# teensyPlayback.net
KiCad netlist of a schematic drawn in Altium Designer
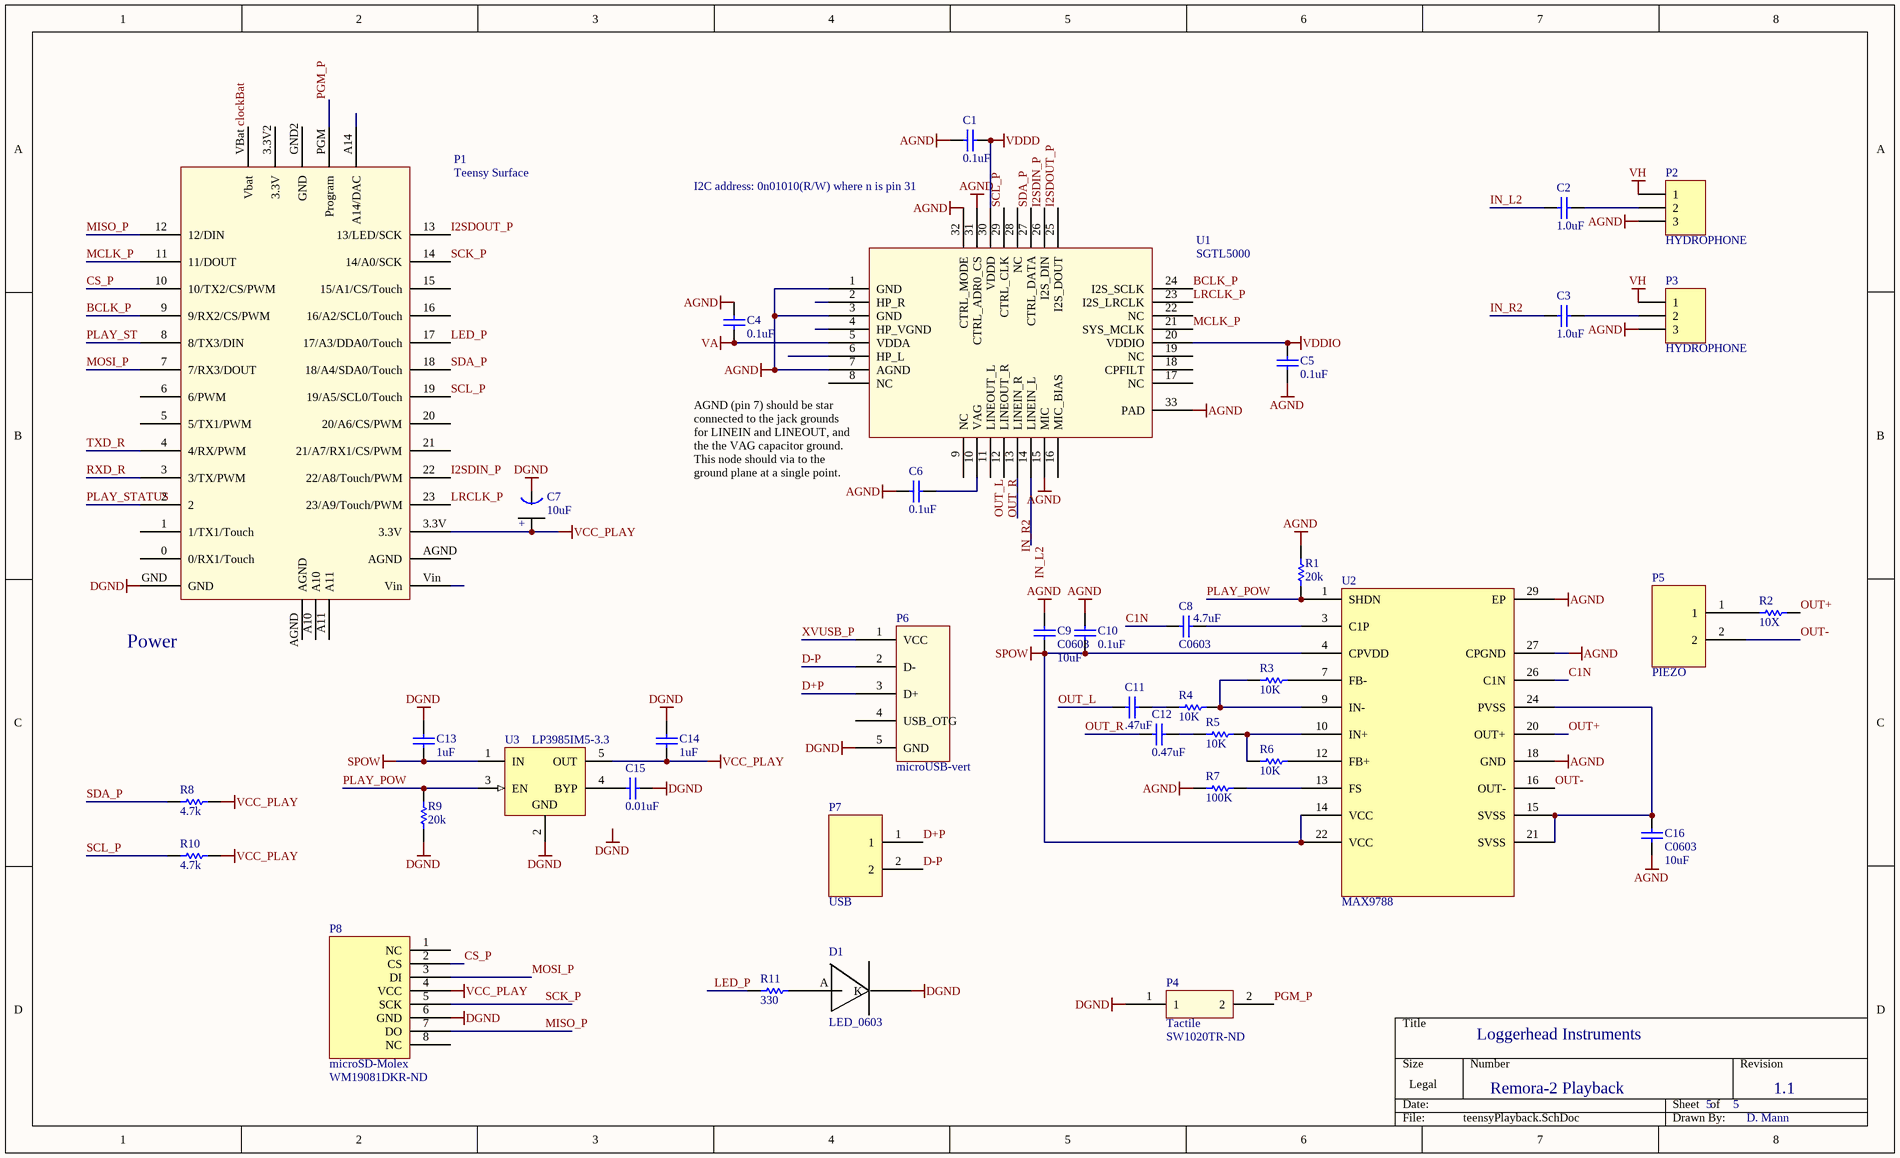
[diagram p0: teensyPlayback.SchDoc]

(export (version "E")
  (design (tool "Eeschema 10.0.6"))
  (components
    (comp (ref "C1")
      (value "0.1uF")
      (footprint "0402")
      (description "Ceramic Chip Capacitor - Standard")
      (fields (field (name "PUBLISHER") "Altium Limited"))
      (libsource (lib "KEMET Chip Capacitor") (part "C0402"))
    )
    (comp (ref "C2")
      (value "1.0uF")
      (footprint "0402")
      (description "Ceramic Chip Capacitor - Standard")
      (fields (field (name "PUBLISHER") "Altium Limited"))
      (libsource (lib "KEMET Chip Capacitor") (part "C0402"))
    )
    (comp (ref "C3")
      (value "1.0uF")
      (footprint "0402")
      (description "Ceramic Chip Capacitor - Standard")
      (fields (field (name "PUBLISHER") "Altium Limited"))
      (libsource (lib "KEMET Chip Capacitor") (part "C0402"))
    )
    (comp (ref "C4")
      (value "0.1uF")
      (footprint "0402")
      (description "Ceramic Chip Capacitor - Standard")
      (fields (field (name "PUBLISHER") "Altium Limited"))
      (libsource (lib "KEMET Chip Capacitor") (part "C0402"))
    )
    (comp (ref "C5")
      (value "0.1uF")
      (footprint "0402")
      (description "Ceramic Chip Capacitor - Standard")
      (fields (field (name "PUBLISHER") "Altium Limited"))
      (libsource (lib "KEMET Chip Capacitor") (part "C0402"))
    )
    (comp (ref "C6")
      (value "0.1uF")
      (footprint "0402")
      (description "Ceramic Chip Capacitor - Standard")
      (fields (field (name "PUBLISHER") "Altium Limited"))
      (libsource (lib "KEMET Chip Capacitor") (part "C0402"))
    )
    (comp (ref "C7") (value "10uF") (footprint "Tant0805") (libsource (lib "Loggerhead") (part "Tant0805")))
    (comp (ref "C8")
      (value "C0603")
      (footprint "0603")
      (description "Ceramic Chip Capacitor - Standard")
      (fields (field (name "ALTIUM_VALUE") "4.7uF") (field (name "PUBLISHER") "Altium Limited"))
      (libsource (lib "KEMET Chip Capacitor") (part "C0603"))
    )
    (comp (ref "C9")
      (value "C0603")
      (footprint "0603")
      (description "Ceramic Chip Capacitor - Standard")
      (fields (field (name "ALTIUM_VALUE") "10uF") (field (name "PUBLISHER") "Altium Limited"))
      (libsource (lib "KEMET Chip Capacitor") (part "C0603"))
    )
    (comp (ref "C10")
      (value "0.1uF")
      (footprint "0402")
      (description "Ceramic Chip Capacitor - Standard")
      (fields (field (name "PUBLISHER") "Altium Limited"))
      (libsource (lib "KEMET Chip Capacitor") (part "C0402"))
    )
    (comp (ref "C11")
      (value ".47uF")
      (footprint "0402")
      (description "Ceramic Chip Capacitor - Standard")
      (fields (field (name "PUBLISHER") "Altium Limited"))
      (libsource (lib "KEMET Chip Capacitor") (part "C0402"))
    )
    (comp (ref "C12")
      (value "0.47uF")
      (footprint "0402")
      (description "Ceramic Chip Capacitor - Standard")
      (fields (field (name "PUBLISHER") "Altium Limited"))
      (libsource (lib "KEMET Chip Capacitor") (part "C0402"))
    )
    (comp (ref "C13")
      (value "1uF")
      (footprint "0402")
      (description "Ceramic Chip Capacitor - Standard")
      (fields (field (name "PUBLISHER") "Altium Limited"))
      (libsource (lib "KEMET Chip Capacitor") (part "C0402"))
    )
    (comp (ref "C14")
      (value "1uF")
      (footprint "0402")
      (description "Ceramic Chip Capacitor - Standard")
      (fields (field (name "PUBLISHER") "Altium Limited"))
      (libsource (lib "KEMET Chip Capacitor") (part "C0402"))
    )
    (comp (ref "C15")
      (value "0.01uF")
      (footprint "0402")
      (description "Ceramic Chip Capacitor - Standard")
      (fields (field (name "PUBLISHER") "Altium Limited"))
      (libsource (lib "KEMET Chip Capacitor") (part "C0402"))
    )
    (comp (ref "C16")
      (value "C0603")
      (footprint "0603")
      (description "Ceramic Chip Capacitor - Standard")
      (fields (field (name "ALTIUM_VALUE") "10uF") (field (name "PUBLISHER") "Altium Limited"))
      (libsource (lib "KEMET Chip Capacitor") (part "C0603"))
    )
    (comp (ref "D1")
      (value "LED_0603")
      (footprint "Diode0603")
      (libsource (lib "Loggerhead") (part "LED_0603"))
    )
    (comp (ref "P1")
      (value "Teensy Surface")
      (footprint "TEENSY3.2_surface_mount")
      (libsource (lib "Teensy") (part "Teensy3.2_surface_mount"))
    )
    (comp (ref "P2")
      (value "HYDROPHONE")
      (footprint "HDR1X3")
      (description "Header, 3-Pin")
      (fields (field (name "PUBLISHER") "Altium Limited"))
      (libsource (lib "Miscellaneous Connectors") (part "Header 3"))
    )
    (comp (ref "P3")
      (value "HYDROPHONE")
      (footprint "HDR1X3")
      (description "Header, 3-Pin")
      (fields (field (name "PUBLISHER") "Altium Limited"))
      (libsource (lib "Miscellaneous Connectors") (part "Header 3"))
    )
    (comp (ref "P4")
      (value "Tactile")
      (footprint "Tactile-B3U-1000")
      (fields (field (name "SUPPLIER PART NUMBER 1") "SW1020TR-ND"))
      (libsource (lib "Loggerhead") (part "Tactile_B3U-1000"))
    )
    (comp (ref "P5")
      (value "PIEZO")
      (footprint "HDR_2x1_2mm")
      (description "Charging Connector")
      (libsource (lib "Loggerhead") (part "HDR_2x1_2mm"))
    )
    (comp (ref "P6")
      (value "microUSB-vert")
      (footprint "MICROUSB-VERT")
      (description "Molex 105133-0011")
      (libsource (lib "Loggerhead") (part "microUSB-vert"))
    )
    (comp (ref "P7")
      (value "USB")
      (footprint "HDR_2x1_2mm")
      (description "Charging Connector")
      (libsource (lib "Loggerhead") (part "HDR_2x1_2mm"))
    )
    (comp (ref "P8")
      (value "microSD-Molex")
      (footprint "microSD_Molex_hinged")
      (fields (field (name "SUPPLIER PART NUMBER 1") "WM19081DKR-ND"))
      (libsource (lib "Loggerhead") (part "microSD_Molex_hinged"))
    )
    (comp (ref "R1")
      (value "20k")
      (footprint "3-0603")
      (fields (field (name "PUBLISHER") "Altium Limited"))
      (libsource (lib "Panasonic Resistor") (part "ERJ3RK"))
    )
    (comp (ref "R2")
      (value "10X")
      (footprint "3-0603")
      (fields (field (name "PUBLISHER") "Altium Limited"))
      (libsource (lib "Panasonic Resistor") (part "ERJ3RK"))
    )
    (comp (ref "R3")
      (value "10K")
      (footprint "3-0603")
      (fields (field (name "PUBLISHER") "Altium Limited"))
      (libsource (lib "Panasonic Resistor") (part "ERJ3RK"))
    )
    (comp (ref "R4")
      (value "10K")
      (footprint "3-0603")
      (fields (field (name "PUBLISHER") "Altium Limited"))
      (libsource (lib "Panasonic Resistor") (part "ERJ3RK"))
    )
    (comp (ref "R5")
      (value "10K")
      (footprint "3-0603")
      (fields (field (name "PUBLISHER") "Altium Limited"))
      (libsource (lib "Panasonic Resistor") (part "ERJ3RK"))
    )
    (comp (ref "R6")
      (value "10K")
      (footprint "3-0603")
      (fields (field (name "PUBLISHER") "Altium Limited"))
      (libsource (lib "Panasonic Resistor") (part "ERJ3RK"))
    )
    (comp (ref "R7")
      (value "100K")
      (footprint "3-0603")
      (fields (field (name "PUBLISHER") "Altium Limited"))
      (libsource (lib "Panasonic Resistor") (part "ERJ3RK"))
    )
    (comp (ref "R8")
      (value "4.7k")
      (footprint "3-0603")
      (fields (field (name "PUBLISHER") "Altium Limited"))
      (libsource (lib "Panasonic Resistor") (part "ERJ3RK"))
    )
    (comp (ref "R9")
      (value "20k")
      (footprint "3-0603")
      (fields (field (name "PUBLISHER") "Altium Limited"))
      (libsource (lib "Panasonic Resistor") (part "ERJ3RK"))
    )
    (comp (ref "R10")
      (value "4.7k")
      (footprint "3-0603")
      (fields (field (name "PUBLISHER") "Altium Limited"))
      (libsource (lib "Panasonic Resistor") (part "ERJ3RK"))
    )
    (comp (ref "R11")
      (value "330")
      (footprint "3-0603")
      (fields (field (name "PUBLISHER") "Altium Limited"))
      (libsource (lib "Panasonic Resistor") (part "ERJ3RK"))
    )
    (comp (ref "U1") (value "SGTL5000") (footprint "QFN32") (libsource (lib "Loggerhead") (part "SGTL5000")))
    (comp (ref "U2")
      (value "MAX9788")
      (footprint "MAX9788")
      (description "audio amp")
      (libsource (lib "Loggerhead") (part "MAX9788"))
    )
    (comp (ref "U3")
      (value "LP3985IM5-3.3")
      (footprint "MF05A_N")
      (description "Micropower, 150mA Low-Noise Ultra Low-Dropout CMOS Voltage Regulator")
      (fields
        (field (name "MANUFACTURER") "National Semiconductor")
        (field (name "DIGIKEYPARTNUMBER") "LP3985IM5-3.3CT-ND")
        (field (name "PUBLISHER") "Altium Limited")
      )
      (libsource (lib "NSC LDO") (part "LP3985IM5-3.3"))
    )
  )
  (nets
    (net (code "1") (name "/BCLK_P") (class "Default")
      (node (ref "P1") (pin "9") (pinfunction "9/RX2/CS/PWM_9") (pintype "passive"))
      (node (ref "U1") (pin "24") (pinfunction "I2S_SCLK_24") (pintype "passive"))
    )
    (net (code "2") (name "/C1N") (class "Default")
      (node (ref "C8") (pin "1") (pinfunction "1_1") (pintype "passive"))
      (node (ref "U2") (pin "26") (pinfunction "C1N_26") (pintype "passive"))
    )
    (net (code "3") (name "/CS_P") (class "Default")
      (node (ref "P1") (pin "10") (pinfunction "10/TX2/CS/PWM_10") (pintype "passive"))
      (node (ref "P8") (pin "2") (pinfunction "CS_2") (pintype "passive"))
    )
    (net (code "4") (name "/D+P") (class "Default")
      (node (ref "P6") (pin "3") (pinfunction "D+_3") (pintype "passive"))
      (node (ref "P7") (pin "1") (pinfunction "1_1") (pintype "passive"))
    )
    (net (code "5") (name "/D-P") (class "Default")
      (node (ref "P6") (pin "2") (pinfunction "D-_2") (pintype "passive"))
      (node (ref "P7") (pin "2") (pinfunction "2_2") (pintype "passive"))
    )
    (net (code "6") (name "/I2SDIN_P") (class "Default")
      (node (ref "P1") (pin "22") (pinfunction "22/A8/Touch/PWM_22") (pintype "passive"))
      (node (ref "U1") (pin "26") (pinfunction "I2S_DIN_26") (pintype "passive"))
    )
    (net (code "7") (name "/I2SDOUT_P") (class "Default")
      (node (ref "P1") (pin "13") (pinfunction "13/LED/SCK_13") (pintype "passive"))
      (node (ref "U1") (pin "25") (pinfunction "I2S_DOUT_25") (pintype "passive"))
    )
    (net (code "8") (name "/IN_L2") (class "Default")
      (node (ref "C2") (pin "2") (pinfunction "2_2") (pintype "passive"))
      (node (ref "U1") (pin "14") (pinfunction "LINEIN_L_14") (pintype "passive"))
    )
    (net (code "9") (name "/IN_R2") (class "Default")
      (node (ref "C3") (pin "2") (pinfunction "2_2") (pintype "passive"))
      (node (ref "U1") (pin "13") (pinfunction "LINEIN_R_13") (pintype "passive"))
    )
    (net (code "10") (name "/LED_P") (class "Default")
      (node (ref "P1") (pin "17") (pinfunction "17/A3/DDA0/Touch_17") (pintype "passive"))
      (node (ref "R11") (pin "1") (pinfunction "1_1") (pintype "passive"))
    )
    (net (code "11") (name "/LRCLK_P") (class "Default")
      (node (ref "P1") (pin "23") (pinfunction "23/A9/Touch/PWM_23") (pintype "passive"))
      (node (ref "U1") (pin "23") (pinfunction "I2S_LRCLK_23") (pintype "passive"))
    )
    (net (code "12") (name "/MCLK_P") (class "Default")
      (node (ref "P1") (pin "11") (pinfunction "11/DOUT_11") (pintype "passive"))
      (node (ref "U1") (pin "21") (pinfunction "SYS_MCLK_21") (pintype "passive"))
    )
    (net (code "13") (name "/MISO_P") (class "Default")
      (node (ref "P1") (pin "12") (pinfunction "12/DIN_12") (pintype "passive"))
      (node (ref "P8") (pin "7") (pinfunction "DO_7") (pintype "passive"))
    )
    (net (code "14") (name "/MOSI_P") (class "Default")
      (node (ref "P1") (pin "7") (pinfunction "7/RX3/DOUT_7") (pintype "passive"))
      (node (ref "P8") (pin "3") (pinfunction "DI_3") (pintype "passive"))
    )
    (net (code "15") (name "/OUT+") (class "Default")
      (node (ref "R2") (pin "1") (pinfunction "1_1") (pintype "passive"))
      (node (ref "U2") (pin "20") (pinfunction "OUT+_20") (pintype "passive"))
    )
    (net (code "16") (name "/OUT-") (class "Default")
      (node (ref "P5") (pin "2") (pinfunction "2_2") (pintype "passive"))
      (node (ref "U2") (pin "16") (pinfunction "OUT-_16") (pintype "passive"))
    )
    (net (code "17") (name "/OUT_L") (class "Default")
      (node (ref "C11") (pin "2") (pinfunction "2_2") (pintype "passive"))
      (node (ref "U1") (pin "11") (pinfunction "LINEOUT_L_11") (pintype "passive"))
    )
    (net (code "18") (name "/OUT_R") (class "Default")
      (node (ref "C12") (pin "2") (pinfunction "2_2") (pintype "passive"))
      (node (ref "U1") (pin "12") (pinfunction "LINEOUT_R_12") (pintype "passive"))
    )
    (net (code "19") (name "/PGM_P") (class "Default")
      (node (ref "P1") (pin "PGM") (pinfunction "Program_PGM") (pintype "passive"))
      (node (ref "P4") (pin "2") (pinfunction "2_2") (pintype "passive"))
    )
    (net (code "20") (name "/PLAY_POW") (class "Default")
      (node (ref "R1") (pin "2") (pinfunction "2_2") (pintype "passive"))
      (node (ref "R9") (pin "2") (pinfunction "2_2") (pintype "passive"))
      (node (ref "U2") (pin "1") (pinfunction "SHDN_1") (pintype "passive"))
      (node (ref "U3") (pin "3") (pinfunction "EN_3") (pintype "input"))
    )
    (net (code "21") (name "/PLAY_ST") (class "Default")
      (node (ref "P1") (pin "8") (pinfunction "8/TX3/DIN_8") (pintype "passive"))
    )
    (net (code "22") (name "/PLAY_STATUS") (class "Default")
      (node (ref "P1") (pin "2") (pinfunction "2_2") (pintype "passive"))
    )
    (net (code "23") (name "/RXD_R") (class "Default")
      (node (ref "P1") (pin "3") (pinfunction "3/TX/PWM_3") (pintype "passive"))
    )
    (net (code "24") (name "/SCK_P") (class "Default")
      (node (ref "P1") (pin "14") (pinfunction "14/A0/SCK_14") (pintype "passive"))
      (node (ref "P8") (pin "5") (pinfunction "SCK_5") (pintype "passive"))
    )
    (net (code "25") (name "/SCL_P") (class "Default")
      (node (ref "P1") (pin "19") (pinfunction "19/A5/SCL0/Touch_19") (pintype "passive"))
      (node (ref "R10") (pin "1") (pinfunction "1_1") (pintype "passive"))
      (node (ref "U1") (pin "29") (pinfunction "CTRL_CLK_29") (pintype "passive"))
    )
    (net (code "26") (name "/SDA_P") (class "Default")
      (node (ref "P1") (pin "18") (pinfunction "18/A4/SDA0/Touch_18") (pintype "passive"))
      (node (ref "R8") (pin "1") (pinfunction "1_1") (pintype "passive"))
      (node (ref "U1") (pin "27") (pinfunction "CTRL_DATA_27") (pintype "passive"))
    )
    (net (code "27") (name "/TXD_R") (class "Default")
      (node (ref "P1") (pin "4") (pinfunction "4/RX/PWM_4") (pintype "passive"))
    )
    (net (code "28") (name "/XVUSB_P") (class "Default")
      (node (ref "P6") (pin "1") (pinfunction "VCC_1") (pintype "passive"))
    )
    (net (code "29") (name "/clockBat") (class "Default")
      (node (ref "P1") (pin "VBat") (pinfunction "Vbat_VBat") (pintype "passive"))
    )
    (net (code "30") (name "AGND") (class "Default")
      (node (ref "C1") (pin "2") (pinfunction "2_2") (pintype "passive"))
      (node (ref "C10") (pin "2") (pinfunction "2_2") (pintype "passive"))
      (node (ref "C16") (pin "1") (pinfunction "1_1") (pintype "passive"))
      (node (ref "C4") (pin "2") (pinfunction "2_2") (pintype "passive"))
      (node (ref "C5") (pin "2") (pinfunction "2_2") (pintype "passive"))
      (node (ref "C6") (pin "2") (pinfunction "2_2") (pintype "passive"))
      (node (ref "C9") (pin "1") (pinfunction "1_1") (pintype "passive"))
      (node (ref "P2") (pin "3") (pinfunction "3_3") (pintype "passive"))
      (node (ref "P3") (pin "3") (pinfunction "3_3") (pintype "passive"))
      (node (ref "R1") (pin "1") (pinfunction "1_1") (pintype "passive"))
      (node (ref "R7") (pin "1") (pinfunction "1_1") (pintype "passive"))
      (node (ref "U1") (pin "1") (pinfunction "GND_1") (pintype "passive"))
      (node (ref "U1") (pin "15") (pinfunction "MIC_15") (pintype "passive"))
      (node (ref "U1") (pin "3") (pinfunction "GND_3") (pintype "passive"))
      (node (ref "U1") (pin "31") (pinfunction "CTRL_ADR0_CS_31") (pintype "passive"))
      (node (ref "U1") (pin "32") (pinfunction "CTRL_MODE_32") (pintype "passive"))
      (node (ref "U1") (pin "33") (pinfunction "PAD_33") (pintype "passive"))
      (node (ref "U1") (pin "7") (pinfunction "AGND_7") (pintype "passive"))
      (node (ref "U2") (pin "18") (pinfunction "GND_18") (pintype "passive"))
      (node (ref "U2") (pin "27") (pinfunction "CPGND_27") (pintype "passive"))
      (node (ref "U2") (pin "29") (pinfunction "EP_29") (pintype "passive"))
    )
    (net (code "31") (name "DGND") (class "Default")
      (node (ref "C13") (pin "2") (pinfunction "2_2") (pintype "passive"))
      (node (ref "C14") (pin "2") (pinfunction "2_2") (pintype "passive"))
      (node (ref "C15") (pin "2") (pinfunction "2_2") (pintype "passive"))
      (node (ref "C7") (pin "1") (pinfunction "GND_1") (pintype "passive"))
      (node (ref "D1") (pin "K") (pinfunction "K_K") (pintype "passive"))
      (node (ref "P1") (pin "GND") (pinfunction "GND_GND") (pintype "passive"))
      (node (ref "P4") (pin "1") (pinfunction "1_1") (pintype "passive"))
      (node (ref "P6") (pin "5") (pinfunction "GND_5") (pintype "passive"))
      (node (ref "P8") (pin "6") (pinfunction "GND_6") (pintype "passive"))
      (node (ref "R9") (pin "1") (pinfunction "1_1") (pintype "passive"))
      (node (ref "U3") (pin "2") (pinfunction "GND_2") (pintype "power_in"))
    )
    (net (code "32") (name "Net-(C2-Pad1)") (class "Default")
      (node (ref "C2") (pin "1") (pinfunction "1_1") (pintype "passive"))
      (node (ref "P2") (pin "2") (pinfunction "2_2") (pintype "passive"))
    )
    (net (code "33") (name "Net-(C3-Pad1)") (class "Default")
      (node (ref "C3") (pin "1") (pinfunction "1_1") (pintype "passive"))
      (node (ref "P3") (pin "2") (pinfunction "2_2") (pintype "passive"))
    )
    (net (code "34") (name "Net-(C11-Pad1)") (class "Default")
      (node (ref "C11") (pin "1") (pinfunction "1_1") (pintype "passive"))
      (node (ref "R4") (pin "1") (pinfunction "1_1") (pintype "passive"))
    )
    (net (code "35") (name "Net-(C12-Pad1)") (class "Default")
      (node (ref "C12") (pin "1") (pinfunction "1_1") (pintype "passive"))
      (node (ref "R5") (pin "1") (pinfunction "1_1") (pintype "passive"))
    )
    (net (code "36") (name "Net-(D1-PadA)") (class "Default")
      (node (ref "D1") (pin "A") (pinfunction "A_A") (pintype "passive"))
      (node (ref "R11") (pin "2") (pinfunction "2_2") (pintype "passive"))
    )
    (net (code "37") (name "Net-(P5-Pad1)") (class "Default")
      (node (ref "P5") (pin "1") (pinfunction "1_1") (pintype "passive"))
      (node (ref "R2") (pin "2") (pinfunction "2_2") (pintype "passive"))
    )
    (net (code "38") (name "Net-(U1-VAG)") (class "Default")
      (node (ref "C6") (pin "1") (pinfunction "1_1") (pintype "passive"))
      (node (ref "U1") (pin "10") (pinfunction "VAG_10") (pintype "passive"))
    )
    (net (code "39") (name "Net-(U2-C1P)") (class "Default")
      (node (ref "C8") (pin "2") (pinfunction "2_2") (pintype "passive"))
      (node (ref "U2") (pin "3") (pinfunction "C1P_3") (pintype "passive"))
    )
    (net (code "40") (name "Net-(U2-FB+)") (class "Default")
      (node (ref "R6") (pin "2") (pinfunction "2_2") (pintype "passive"))
      (node (ref "U2") (pin "12") (pinfunction "FB+_12") (pintype "passive"))
    )
    (net (code "41") (name "Net-(U2-FB-)") (class "Default")
      (node (ref "R3") (pin "2") (pinfunction "2_2") (pintype "passive"))
      (node (ref "U2") (pin "7") (pinfunction "FB-_7") (pintype "passive"))
    )
    (net (code "42") (name "Net-(U2-FS)") (class "Default")
      (node (ref "R7") (pin "2") (pinfunction "2_2") (pintype "passive"))
      (node (ref "U2") (pin "13") (pinfunction "FS_13") (pintype "passive"))
    )
    (net (code "43") (name "Net-(U2-IN+)") (class "Default")
      (node (ref "R5") (pin "2") (pinfunction "2_2") (pintype "passive"))
      (node (ref "R6") (pin "1") (pinfunction "1_1") (pintype "passive"))
      (node (ref "U2") (pin "10") (pinfunction "IN+_10") (pintype "passive"))
    )
    (net (code "44") (name "Net-(U2-IN-)") (class "Default")
      (node (ref "R3") (pin "1") (pinfunction "1_1") (pintype "passive"))
      (node (ref "R4") (pin "2") (pinfunction "2_2") (pintype "passive"))
      (node (ref "U2") (pin "9") (pinfunction "IN-_9") (pintype "passive"))
    )
    (net (code "45") (name "Net-(U2-PVSS)") (class "Default")
      (node (ref "C16") (pin "2") (pinfunction "2_2") (pintype "passive"))
      (node (ref "U2") (pin "15") (pinfunction "SVSS_15") (pintype "passive"))
      (node (ref "U2") (pin "21") (pinfunction "SVSS_21") (pintype "passive"))
      (node (ref "U2") (pin "24") (pinfunction "PVSS_24") (pintype "passive"))
    )
    (net (code "46") (name "Net-(U3-BYP)") (class "Default")
      (node (ref "C15") (pin "1") (pinfunction "1_1") (pintype "passive"))
      (node (ref "U3") (pin "4") (pinfunction "BYP_4") (pintype "passive"))
    )
    (net (code "47") (name "SPOW") (class "Default")
      (node (ref "C10") (pin "1") (pinfunction "1_1") (pintype "passive"))
      (node (ref "C13") (pin "1") (pinfunction "1_1") (pintype "passive"))
      (node (ref "C9") (pin "2") (pinfunction "2_2") (pintype "passive"))
      (node (ref "U2") (pin "14") (pinfunction "VCC_14") (pintype "passive"))
      (node (ref "U2") (pin "22") (pinfunction "VCC_22") (pintype "passive"))
      (node (ref "U2") (pin "4") (pinfunction "CPVDD_4") (pintype "passive"))
      (node (ref "U3") (pin "1") (pinfunction "IN_1") (pintype "power_in"))
    )
    (net (code "48") (name "VA") (class "Default")
      (node (ref "C4") (pin "1") (pinfunction "1_1") (pintype "passive"))
      (node (ref "U1") (pin "5") (pinfunction "VDDA_5") (pintype "passive"))
    )
    (net (code "49") (name "VCC_PLAY") (class "Default")
      (node (ref "C14") (pin "1") (pinfunction "1_1") (pintype "passive"))
      (node (ref "C7") (pin "2") (pinfunction "+_2") (pintype "passive"))
      (node (ref "P1") (pin "3.3V") (pinfunction "3.3V_3.3V") (pintype "passive"))
      (node (ref "P8") (pin "4") (pinfunction "VCC_4") (pintype "passive"))
      (node (ref "R10") (pin "2") (pinfunction "2_2") (pintype "passive"))
      (node (ref "R8") (pin "2") (pinfunction "2_2") (pintype "passive"))
      (node (ref "U3") (pin "5") (pinfunction "OUT_5") (pintype "power_in"))
    )
    (net (code "50") (name "VDDD") (class "Default")
      (node (ref "C1") (pin "1") (pinfunction "1_1") (pintype "passive"))
      (node (ref "U1") (pin "30") (pinfunction "VDDD_30") (pintype "passive"))
    )
    (net (code "51") (name "VDDIO") (class "Default")
      (node (ref "C5") (pin "1") (pinfunction "1_1") (pintype "passive"))
      (node (ref "U1") (pin "20") (pinfunction "VDDIO_20") (pintype "passive"))
    )
    (net (code "52") (name "VH") (class "Default")
      (node (ref "P2") (pin "1") (pinfunction "1_1") (pintype "passive"))
      (node (ref "P3") (pin "1") (pinfunction "1_1") (pintype "passive"))
    )
    (net (code "53") (name "unconnected-(P1-0{slash}RX1{slash}Touch-Pad0)") (class "Default")
      (node (ref "P1") (pin "0") (pinfunction "0/RX1/Touch_0") (pintype "passive"))
    )
    (net (code "54") (name "unconnected-(P1-1{slash}TX1{slash}Touch-Pad1)") (class "Default")
      (node (ref "P1") (pin "1") (pinfunction "1/TX1/Touch_1") (pintype "passive"))
    )
    (net (code "55") (name "unconnected-(P1-3.3V-Pad3.3V2)") (class "Default")
      (node (ref "P1") (pin "3.3V2") (pinfunction "3.3V_3.3V2") (pintype "passive"))
    )
    (net (code "56") (name "unconnected-(P1-5{slash}TX1{slash}PWM-Pad5)") (class "Default")
      (node (ref "P1") (pin "5") (pinfunction "5/TX1/PWM_5") (pintype "passive"))
    )
    (net (code "57") (name "unconnected-(P1-6{slash}PWM-Pad6)") (class "Default")
      (node (ref "P1") (pin "6") (pinfunction "6/PWM_6") (pintype "passive"))
    )
    (net (code "58") (name "unconnected-(P1-15{slash}A1{slash}CS{slash}Touch-Pad15)") (class "Default")
      (node (ref "P1") (pin "15") (pinfunction "15/A1/CS/Touch_15") (pintype "passive"))
    )
    (net (code "59") (name "unconnected-(P1-16{slash}A2{slash}SCL0{slash}Touch-Pad16)") (class "Default")
      (node (ref "P1") (pin "16") (pinfunction "16/A2/SCL0/Touch_16") (pintype "passive"))
    )
    (net (code "60") (name "unconnected-(P1-20{slash}A6{slash}CS{slash}PWM-Pad20)") (class "Default")
      (node (ref "P1") (pin "20") (pinfunction "20/A6/CS/PWM_20") (pintype "passive"))
    )
    (net (code "61") (name "unconnected-(P1-21{slash}A7{slash}RX1{slash}CS{slash}PWM-Pad21)") (class "Default")
      (node (ref "P1") (pin "21") (pinfunction "21/A7/RX1/CS/PWM_21") (pintype "passive"))
    )
    (net (code "62") (name "unconnected-(P1-A14{slash}DAC-PadA14)") (class "Default")
      (node (ref "P1") (pin "A14") (pinfunction "A14/DAC_A14") (pintype "passive"))
    )
    (net (code "63") (name "unconnected-(P1-GND-PadGND2)") (class "Default")
      (node (ref "P1") (pin "GND2") (pinfunction "GND_GND2") (pintype "passive"))
    )
    (net (code "64") (name "unconnected-(P1-PadA10)") (class "Default")
      (node (ref "P1") (pin "A10") (pinfunction "A10_A10") (pintype "passive"))
    )
    (net (code "65") (name "unconnected-(P1-PadA11)") (class "Default")
      (node (ref "P1") (pin "A11") (pinfunction "A11_A11") (pintype "passive"))
    )
    (net (code "66") (name "unconnected-(P1-PadAGND)") (class "Default")
      (node (ref "P1") (pin "AGND") (pinfunction "AGND_AGND") (pintype "passive"))
    )
    (net (code "67") (name "unconnected-(P1-PadAGND)_1") (class "Default")
      (node (ref "P1") (pin "AGND") (pinfunction "AGND_AGND") (pintype "passive"))
    )
    (net (code "68") (name "unconnected-(P1-PadVin)") (class "Default")
      (node (ref "P1") (pin "Vin") (pinfunction "Vin_Vin") (pintype "passive"))
    )
    (net (code "69") (name "unconnected-(P6-USB_OTG-Pad4)") (class "Default")
      (node (ref "P6") (pin "4") (pinfunction "USB_OTG_4") (pintype "passive"))
    )
    (net (code "70") (name "unconnected-(P8-NC-Pad1)") (class "Default")
      (node (ref "P8") (pin "1") (pinfunction "NC_1") (pintype "passive"))
    )
    (net (code "71") (name "unconnected-(P8-NC-Pad8)") (class "Default")
      (node (ref "P8") (pin "8") (pinfunction "NC_8") (pintype "passive"))
    )
    (net (code "72") (name "unconnected-(U1-CPFILT-Pad18)") (class "Default")
      (node (ref "U1") (pin "18") (pinfunction "CPFILT_18") (pintype "passive"))
    )
    (net (code "73") (name "unconnected-(U1-HP_L-Pad6)") (class "Default")
      (node (ref "U1") (pin "6") (pinfunction "HP_L_6") (pintype "passive"))
    )
    (net (code "74") (name "unconnected-(U1-HP_R-Pad2)") (class "Default")
      (node (ref "U1") (pin "2") (pinfunction "HP_R_2") (pintype "passive"))
    )
    (net (code "75") (name "unconnected-(U1-HP_VGND-Pad4)") (class "Default")
      (node (ref "U1") (pin "4") (pinfunction "HP_VGND_4") (pintype "passive"))
    )
    (net (code "76") (name "unconnected-(U1-MIC_BIAS-Pad16)") (class "Default")
      (node (ref "U1") (pin "16") (pinfunction "MIC_BIAS_16") (pintype "passive"))
    )
    (net (code "77") (name "unconnected-(U1-NC-Pad8)") (class "Default")
      (node (ref "U1") (pin "8") (pinfunction "NC_8") (pintype "passive"))
    )
    (net (code "78") (name "unconnected-(U1-NC-Pad9)") (class "Default")
      (node (ref "U1") (pin "9") (pinfunction "NC_9") (pintype "passive"))
    )
    (net (code "79") (name "unconnected-(U1-NC-Pad17)") (class "Default")
      (node (ref "U1") (pin "17") (pinfunction "NC_17") (pintype "passive"))
    )
    (net (code "80") (name "unconnected-(U1-NC-Pad19)") (class "Default")
      (node (ref "U1") (pin "19") (pinfunction "NC_19") (pintype "passive"))
    )
    (net (code "81") (name "unconnected-(U1-NC-Pad22)") (class "Default")
      (node (ref "U1") (pin "22") (pinfunction "NC_22") (pintype "passive"))
    )
    (net (code "82") (name "unconnected-(U1-NC-Pad28)") (class "Default")
      (node (ref "U1") (pin "28") (pinfunction "NC_28") (pintype "passive"))
    )
  )
)
